# can_uart.net
KiCad netlist of a schematic drawn in Altium Designer
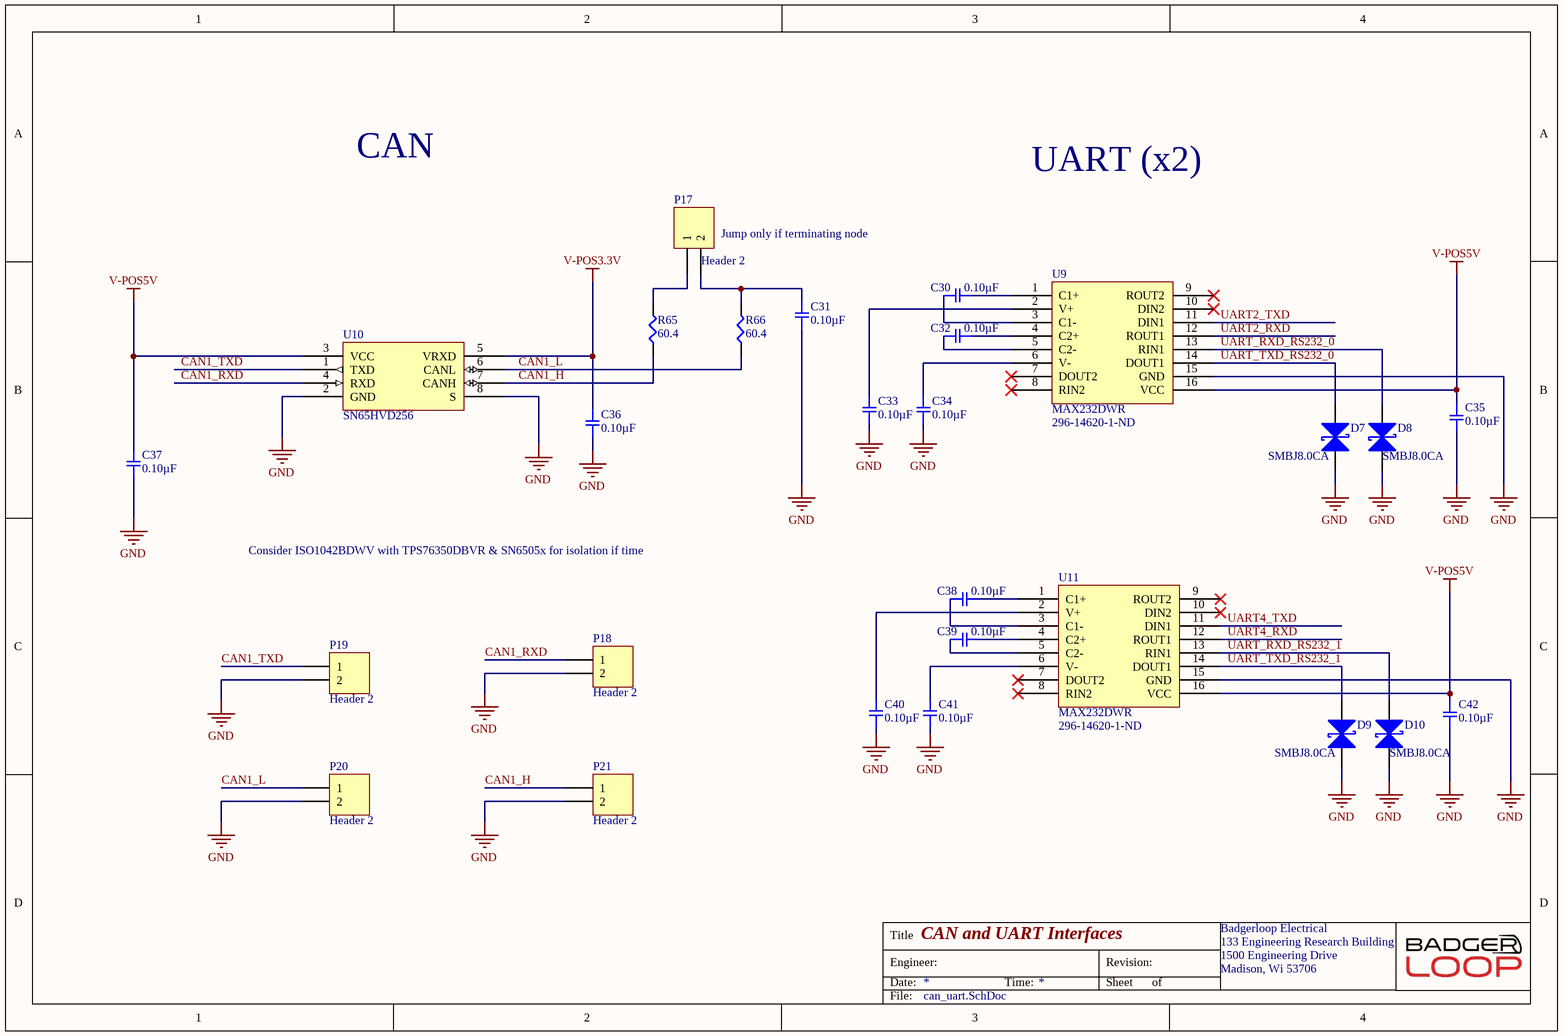
[diagram p0: can_uart.SchDoc]

(export (version "E")
  (design (tool "Eeschema 10.0.6"))
  (components
    (comp (ref "C30")
      (value "0.10µF")
      (footprint "SMD-0805C")
      (description "CAP CER 0.1UF 16V X7R 0805")
      (fields
        (field (name "DIGI-KEY PART NUMBER") "490-12557-1-ND")
        (field (name "PART NUMBER") "GRM219R71C104JA01D")
      )
      (libsource (lib "capacitors") (part "GRM219R71C104JA01D"))
    )
    (comp (ref "C31")
      (value "0.10µF")
      (footprint "SMD-0805C")
      (description "CAP CER 0.1UF 16V X7R 0805")
      (fields
        (field (name "DIGI-KEY PART NUMBER") "490-12557-1-ND")
        (field (name "PART NUMBER") "GRM219R71C104JA01D")
      )
      (libsource (lib "capacitors") (part "GRM219R71C104JA01D"))
    )
    (comp (ref "C32")
      (value "0.10µF")
      (footprint "SMD-0805C")
      (description "CAP CER 0.1UF 16V X7R 0805")
      (fields
        (field (name "DIGI-KEY PART NUMBER") "490-12557-1-ND")
        (field (name "PART NUMBER") "GRM219R71C104JA01D")
      )
      (libsource (lib "capacitors") (part "GRM219R71C104JA01D"))
    )
    (comp (ref "C33")
      (value "0.10µF")
      (footprint "SMD-0805C")
      (description "CAP CER 0.1UF 16V X7R 0805")
      (fields
        (field (name "DIGI-KEY PART NUMBER") "490-12557-1-ND")
        (field (name "PART NUMBER") "GRM219R71C104JA01D")
      )
      (libsource (lib "capacitors") (part "GRM219R71C104JA01D"))
    )
    (comp (ref "C34")
      (value "0.10µF")
      (footprint "SMD-0805C")
      (description "CAP CER 0.1UF 16V X7R 0805")
      (fields
        (field (name "DIGI-KEY PART NUMBER") "490-12557-1-ND")
        (field (name "PART NUMBER") "GRM219R71C104JA01D")
      )
      (libsource (lib "capacitors") (part "GRM219R71C104JA01D"))
    )
    (comp (ref "C35")
      (value "0.10µF")
      (footprint "SMD-0805C")
      (description "CAP CER 0.1UF 25V X7R 0805")
      (fields
        (field (name "DIGI-KEY PART NUMBER") "490-12754-1-ND")
        (field (name "PART NUMBER") "GRM219R71E104KA01D")
      )
      (libsource (lib "capacitors") (part "GRM219R71E104KA01D"))
    )
    (comp (ref "C36")
      (value "0.10µF")
      (footprint "SMD-0805C")
      (description "CAP CER 0.1UF 16V X7R 0805")
      (fields
        (field (name "DIGI-KEY PART NUMBER") "490-12557-1-ND")
        (field (name "PART NUMBER") "GRM219R71C104JA01D")
      )
      (libsource (lib "capacitors") (part "GRM219R71C104JA01D"))
    )
    (comp (ref "C37")
      (value "0.10µF")
      (footprint "SMD-0805C")
      (description "CAP CER 0.1UF 16V X7R 0805")
      (fields
        (field (name "DIGI-KEY PART NUMBER") "490-12557-1-ND")
        (field (name "PART NUMBER") "GRM219R71C104JA01D")
      )
      (libsource (lib "capacitors") (part "GRM219R71C104JA01D"))
    )
    (comp (ref "C38")
      (value "0.10µF")
      (footprint "SMD-0805C")
      (description "CAP CER 0.1UF 16V X7R 0805")
      (fields
        (field (name "DIGI-KEY PART NUMBER") "490-12557-1-ND")
        (field (name "PART NUMBER") "GRM219R71C104JA01D")
      )
      (libsource (lib "capacitors") (part "GRM219R71C104JA01D"))
    )
    (comp (ref "C39")
      (value "0.10µF")
      (footprint "SMD-0805C")
      (description "CAP CER 0.1UF 16V X7R 0805")
      (fields
        (field (name "DIGI-KEY PART NUMBER") "490-12557-1-ND")
        (field (name "PART NUMBER") "GRM219R71C104JA01D")
      )
      (libsource (lib "capacitors") (part "GRM219R71C104JA01D"))
    )
    (comp (ref "C40")
      (value "0.10µF")
      (footprint "SMD-0805C")
      (description "CAP CER 0.1UF 16V X7R 0805")
      (fields
        (field (name "DIGI-KEY PART NUMBER") "490-12557-1-ND")
        (field (name "PART NUMBER") "GRM219R71C104JA01D")
      )
      (libsource (lib "capacitors") (part "GRM219R71C104JA01D"))
    )
    (comp (ref "C41")
      (value "0.10µF")
      (footprint "SMD-0805C")
      (description "CAP CER 0.1UF 16V X7R 0805")
      (fields
        (field (name "DIGI-KEY PART NUMBER") "490-12557-1-ND")
        (field (name "PART NUMBER") "GRM219R71C104JA01D")
      )
      (libsource (lib "capacitors") (part "GRM219R71C104JA01D"))
    )
    (comp (ref "C42")
      (value "0.10µF")
      (footprint "SMD-0805C")
      (description "CAP CER 0.1UF 25V X7R 0805")
      (fields
        (field (name "DIGI-KEY PART NUMBER") "490-12754-1-ND")
        (field (name "PART NUMBER") "GRM219R71E104KA01D")
      )
      (libsource (lib "capacitors") (part "GRM219R71E104KA01D"))
    )
    (comp (ref "D7")
      (value "SMBJ8.0CA")
      (footprint "DIOM4436X26N")
      (description "TVS DIODE 8V 13.6V DO214AA")
      (fields (field (name "MANUFACTURER") "Littelfuse"))
      (libsource (lib "misc") (part "SMBJ8.0CA"))
    )
    (comp (ref "D8")
      (value "SMBJ8.0CA")
      (footprint "DIOM4436X26N")
      (description "TVS DIODE 8V 13.6V DO214AA")
      (fields (field (name "MANUFACTURER") "Littelfuse"))
      (libsource (lib "misc") (part "SMBJ8.0CA"))
    )
    (comp (ref "D9")
      (value "SMBJ8.0CA")
      (footprint "DIOM4436X26N")
      (description "TVS DIODE 8V 13.6V DO214AA")
      (fields (field (name "MANUFACTURER") "Littelfuse"))
      (libsource (lib "misc") (part "SMBJ8.0CA"))
    )
    (comp (ref "D10")
      (value "SMBJ8.0CA")
      (footprint "DIOM4436X26N")
      (description "TVS DIODE 8V 13.6V DO214AA")
      (fields (field (name "MANUFACTURER") "Littelfuse"))
      (libsource (lib "misc") (part "SMBJ8.0CA"))
    )
    (comp (ref "P17")
      (value "Header 2")
      (footprint "Pin Header 1x2 TH Pitch 2.54mm")
      (description "Header, 2-Pin")
      (fields (field (name "PUBLISHER") "Altium Limited"))
      (libsource (lib "") (part "Header 2_1"))
    )
    (comp (ref "P18")
      (value "Header 2")
      (footprint "Pin Header 1x2 TH Pitch 2.54mm")
      (description "Header, 2-Pin")
      (fields (field (name "PUBLISHER") "Altium Limited"))
      (libsource (lib "connector") (part "Header 2"))
    )
    (comp (ref "P19")
      (value "Header 2")
      (footprint "Pin Header 1x2 TH Pitch 2.54mm")
      (description "Header, 2-Pin")
      (fields (field (name "PUBLISHER") "Altium Limited"))
      (libsource (lib "connector") (part "Header 2"))
    )
    (comp (ref "P20")
      (value "Header 2")
      (footprint "Pin Header 1x2 TH Pitch 2.54mm")
      (description "Header, 2-Pin")
      (fields (field (name "PUBLISHER") "Altium Limited"))
      (libsource (lib "connector") (part "Header 2"))
    )
    (comp (ref "P21")
      (value "Header 2")
      (footprint "Pin Header 1x2 TH Pitch 2.54mm")
      (description "Header, 2-Pin")
      (fields (field (name "PUBLISHER") "Altium Limited"))
      (libsource (lib "connector") (part "Header 2"))
    )
    (comp (ref "R65")
      (value "60.4")
      (footprint "SMD-1206-RES")
      (description "RES SMD 60.4 OHM 1% 1/4W 1206")
      (fields
        (field (name "PART NUMBER") "ERJ-8ENF60R4V")
        (field (name "DIGI-KEY PART NUMBER") "P60.4FCT-ND")
      )
      (libsource (lib "resistors") (part "ERJ-8ENF60R4V"))
    )
    (comp (ref "R66")
      (value "60.4")
      (footprint "SMD-1206-RES")
      (description "RES SMD 60.4 OHM 1% 1/4W 1206")
      (fields
        (field (name "PART NUMBER") "ERJ-8ENF60R4V")
        (field (name "DIGI-KEY PART NUMBER") "P60.4FCT-ND")
      )
      (libsource (lib "resistors") (part "ERJ-8ENF60R4V"))
    )
    (comp (ref "U9")
      (value "MAX232DWR")
      (footprint "SOP127P1060X175-16N")
      (description "IC DRVR/RCVR MULTCH RS232 16SOIC")
      (fields
        (field (name "MANUFACTURER") "Texas Instruments")
        (field (name "SUPPLIER PART NUMBER 1") "296-14620-1-ND")
      )
      (libsource (lib "ic") (part "MAX232DWR"))
    )
    (comp (ref "U10")
      (value "SN65HVD256")
      (footprint "SOIC127P610X280-8N")
      (description "IC TXRX CAN 5V HS 8SOIC")
      (fields (field (name "MANUFACTURER") "TI"))
      (libsource (lib "ic") (part "SN65HVD256"))
    )
    (comp (ref "U11")
      (value "MAX232DWR")
      (footprint "SOP127P1060X175-16N")
      (description "IC DRVR/RCVR MULTCH RS232 16SOIC")
      (fields
        (field (name "MANUFACTURER") "Texas Instruments")
        (field (name "SUPPLIER PART NUMBER 1") "296-14620-1-ND")
      )
      (libsource (lib "ic") (part "MAX232DWR"))
    )
  )
  (nets
    (net (code "1") (name "/CAN1_H") (class "Default")
      (node (ref "P21") (pin "1") (pinfunction "1_1") (pintype "passive"))
      (node (ref "R65") (pin "1") (pinfunction "1_1") (pintype "passive"))
      (node (ref "U10") (pin "7") (pinfunction "CANH_7") (pintype "bidirectional"))
    )
    (net (code "2") (name "/CAN1_L") (class "Default")
      (node (ref "P20") (pin "1") (pinfunction "1_1") (pintype "passive"))
      (node (ref "R66") (pin "1") (pinfunction "1_1") (pintype "passive"))
      (node (ref "U10") (pin "6") (pinfunction "CANL_6") (pintype "bidirectional"))
    )
    (net (code "3") (name "/CAN1_RXD") (class "Default")
      (node (ref "P18") (pin "1") (pinfunction "1_1") (pintype "passive"))
      (node (ref "U10") (pin "4") (pinfunction "RXD_4") (pintype "input"))
    )
    (net (code "4") (name "/CAN1_TXD") (class "Default")
      (node (ref "P19") (pin "1") (pinfunction "1_1") (pintype "passive"))
      (node (ref "U10") (pin "1") (pinfunction "TXD_1") (pintype "output"))
    )
    (net (code "5") (name "/UART2_RXD") (class "Default")
      (node (ref "U9") (pin "12") (pinfunction "ROUT1_12") (pintype "passive"))
    )
    (net (code "6") (name "/UART2_TXD") (class "Default")
      (node (ref "U9") (pin "11") (pinfunction "DIN1_11") (pintype "passive"))
    )
    (net (code "7") (name "/UART4_RXD") (class "Default")
      (node (ref "U11") (pin "12") (pinfunction "ROUT1_12") (pintype "passive"))
    )
    (net (code "8") (name "/UART4_TXD") (class "Default")
      (node (ref "U11") (pin "11") (pinfunction "DIN1_11") (pintype "passive"))
    )
    (net (code "9") (name "/UART_RXD_RS232_0") (class "Default")
      (node (ref "D8") (pin "2") (pinfunction "K_2") (pintype "passive"))
      (node (ref "U9") (pin "13") (pinfunction "RIN1_13") (pintype "passive"))
    )
    (net (code "10") (name "/UART_RXD_RS232_1") (class "Default")
      (node (ref "D10") (pin "2") (pinfunction "K_2") (pintype "passive"))
      (node (ref "U11") (pin "13") (pinfunction "RIN1_13") (pintype "passive"))
    )
    (net (code "11") (name "/UART_TXD_RS232_0") (class "Default")
      (node (ref "D7") (pin "2") (pinfunction "K_2") (pintype "passive"))
      (node (ref "U9") (pin "14") (pinfunction "DOUT1_14") (pintype "passive"))
    )
    (net (code "12") (name "/UART_TXD_RS232_1") (class "Default")
      (node (ref "D9") (pin "2") (pinfunction "K_2") (pintype "passive"))
      (node (ref "U11") (pin "14") (pinfunction "DOUT1_14") (pintype "passive"))
    )
    (net (code "13") (name "GND") (class "Default")
      (node (ref "C31") (pin "1") (pinfunction "1_1") (pintype "passive"))
      (node (ref "C33") (pin "1") (pinfunction "1_1") (pintype "passive"))
      (node (ref "C34") (pin "1") (pinfunction "1_1") (pintype "passive"))
      (node (ref "C35") (pin "2") (pinfunction "2_2") (pintype "passive"))
      (node (ref "C36") (pin "1") (pinfunction "1_1") (pintype "passive"))
      (node (ref "C37") (pin "1") (pinfunction "1_1") (pintype "passive"))
      (node (ref "C40") (pin "1") (pinfunction "1_1") (pintype "passive"))
      (node (ref "C41") (pin "1") (pinfunction "1_1") (pintype "passive"))
      (node (ref "C42") (pin "2") (pinfunction "2_2") (pintype "passive"))
      (node (ref "D10") (pin "1") (pinfunction "A_1") (pintype "passive"))
      (node (ref "D7") (pin "1") (pinfunction "A_1") (pintype "passive"))
      (node (ref "D8") (pin "1") (pinfunction "A_1") (pintype "passive"))
      (node (ref "D9") (pin "1") (pinfunction "A_1") (pintype "passive"))
      (node (ref "P18") (pin "2") (pinfunction "2_2") (pintype "passive"))
      (node (ref "P19") (pin "2") (pinfunction "2_2") (pintype "passive"))
      (node (ref "P20") (pin "2") (pinfunction "2_2") (pintype "passive"))
      (node (ref "P21") (pin "2") (pinfunction "2_2") (pintype "passive"))
      (node (ref "U10") (pin "2") (pinfunction "GND_2") (pintype "power_in"))
      (node (ref "U10") (pin "8") (pinfunction "S_8") (pintype "passive"))
      (node (ref "U11") (pin "15") (pinfunction "GND_15") (pintype "passive"))
      (node (ref "U9") (pin "15") (pinfunction "GND_15") (pintype "passive"))
    )
    (net (code "14") (name "Net-(C31-Pad2)") (class "Default")
      (node (ref "C31") (pin "2") (pinfunction "2_2") (pintype "passive"))
      (node (ref "P17") (pin "2") (pinfunction "2_2") (pintype "passive"))
      (node (ref "R66") (pin "2") (pinfunction "2_2") (pintype "passive"))
    )
    (net (code "15") (name "Net-(P17-Pad1)") (class "Default")
      (node (ref "P17") (pin "1") (pinfunction "1_1") (pintype "passive"))
      (node (ref "R65") (pin "2") (pinfunction "2_2") (pintype "passive"))
    )
    (net (code "16") (name "Net-(U9-C1+)") (class "Default")
      (node (ref "C30") (pin "2") (pinfunction "2_2") (pintype "passive"))
      (node (ref "U9") (pin "1") (pinfunction "C1+_1") (pintype "passive"))
    )
    (net (code "17") (name "Net-(U9-C1-)") (class "Default")
      (node (ref "C30") (pin "1") (pinfunction "1_1") (pintype "passive"))
      (node (ref "U9") (pin "3") (pinfunction "C1-_3") (pintype "passive"))
    )
    (net (code "18") (name "Net-(U9-C2+)") (class "Default")
      (node (ref "C32") (pin "2") (pinfunction "2_2") (pintype "passive"))
      (node (ref "U9") (pin "4") (pinfunction "C2+_4") (pintype "passive"))
    )
    (net (code "19") (name "Net-(U9-C2-)") (class "Default")
      (node (ref "C32") (pin "1") (pinfunction "1_1") (pintype "passive"))
      (node (ref "U9") (pin "5") (pinfunction "C2-_5") (pintype "passive"))
    )
    (net (code "20") (name "Net-(U9-V+)") (class "Default")
      (node (ref "C33") (pin "2") (pinfunction "2_2") (pintype "passive"))
      (node (ref "U9") (pin "2") (pinfunction "V+_2") (pintype "passive"))
    )
    (net (code "21") (name "Net-(U9-V-)") (class "Default")
      (node (ref "C34") (pin "2") (pinfunction "2_2") (pintype "passive"))
      (node (ref "U9") (pin "6") (pinfunction "V-_6") (pintype "passive"))
    )
    (net (code "22") (name "Net-(U11-C1+)") (class "Default")
      (node (ref "C38") (pin "2") (pinfunction "2_2") (pintype "passive"))
      (node (ref "U11") (pin "1") (pinfunction "C1+_1") (pintype "passive"))
    )
    (net (code "23") (name "Net-(U11-C1-)") (class "Default")
      (node (ref "C38") (pin "1") (pinfunction "1_1") (pintype "passive"))
      (node (ref "U11") (pin "3") (pinfunction "C1-_3") (pintype "passive"))
    )
    (net (code "24") (name "Net-(U11-C2+)") (class "Default")
      (node (ref "C39") (pin "2") (pinfunction "2_2") (pintype "passive"))
      (node (ref "U11") (pin "4") (pinfunction "C2+_4") (pintype "passive"))
    )
    (net (code "25") (name "Net-(U11-C2-)") (class "Default")
      (node (ref "C39") (pin "1") (pinfunction "1_1") (pintype "passive"))
      (node (ref "U11") (pin "5") (pinfunction "C2-_5") (pintype "passive"))
    )
    (net (code "26") (name "Net-(U11-V+)") (class "Default")
      (node (ref "C40") (pin "2") (pinfunction "2_2") (pintype "passive"))
      (node (ref "U11") (pin "2") (pinfunction "V+_2") (pintype "passive"))
    )
    (net (code "27") (name "Net-(U11-V-)") (class "Default")
      (node (ref "C41") (pin "2") (pinfunction "2_2") (pintype "passive"))
      (node (ref "U11") (pin "6") (pinfunction "V-_6") (pintype "passive"))
    )
    (net (code "28") (name "V-POS3.3V") (class "Default")
      (node (ref "C36") (pin "2") (pinfunction "2_2") (pintype "passive"))
      (node (ref "U10") (pin "5") (pinfunction "VRXD_5") (pintype "power_in"))
    )
    (net (code "29") (name "V-POS5V") (class "Default")
      (node (ref "C35") (pin "1") (pinfunction "1_1") (pintype "passive"))
      (node (ref "C37") (pin "2") (pinfunction "2_2") (pintype "passive"))
      (node (ref "C42") (pin "1") (pinfunction "1_1") (pintype "passive"))
      (node (ref "U10") (pin "3") (pinfunction "VCC_3") (pintype "power_in"))
      (node (ref "U11") (pin "16") (pinfunction "VCC_16") (pintype "passive"))
      (node (ref "U9") (pin "16") (pinfunction "VCC_16") (pintype "passive"))
    )
    (net (code "30") (name "unconnected-(U9-DIN2-Pad10)") (class "Default")
      (node (ref "U9") (pin "10") (pinfunction "DIN2_10") (pintype "passive+no_connect"))
    )
    (net (code "31") (name "unconnected-(U9-DOUT2-Pad7)") (class "Default")
      (node (ref "U9") (pin "7") (pinfunction "DOUT2_7") (pintype "passive+no_connect"))
    )
    (net (code "32") (name "unconnected-(U9-RIN2-Pad8)") (class "Default")
      (node (ref "U9") (pin "8") (pinfunction "RIN2_8") (pintype "passive+no_connect"))
    )
    (net (code "33") (name "unconnected-(U9-ROUT2-Pad9)") (class "Default")
      (node (ref "U9") (pin "9") (pinfunction "ROUT2_9") (pintype "passive+no_connect"))
    )
    (net (code "34") (name "unconnected-(U11-DIN2-Pad10)") (class "Default")
      (node (ref "U11") (pin "10") (pinfunction "DIN2_10") (pintype "passive+no_connect"))
    )
    (net (code "35") (name "unconnected-(U11-DOUT2-Pad7)") (class "Default")
      (node (ref "U11") (pin "7") (pinfunction "DOUT2_7") (pintype "passive+no_connect"))
    )
    (net (code "36") (name "unconnected-(U11-RIN2-Pad8)") (class "Default")
      (node (ref "U11") (pin "8") (pinfunction "RIN2_8") (pintype "passive+no_connect"))
    )
    (net (code "37") (name "unconnected-(U11-ROUT2-Pad9)") (class "Default")
      (node (ref "U11") (pin "9") (pinfunction "ROUT2_9") (pintype "passive+no_connect"))
    )
  )
)
